# MJE13001_SWITCHING_WITH_FEEDBACK_V2.net
KiCad netlist of a schematic drawn in Altium Designer
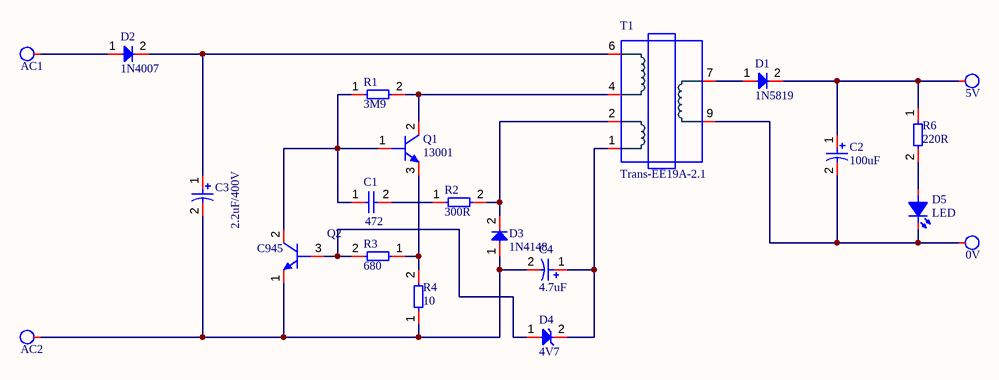
[diagram p0: MJE13001_SWITCHING_WITH_FEEDBACK_V2.SchDoc]

(export (version "E")
  (design (tool "Eeschema 10.0.6"))
  (components
    (comp (ref "0V")
      (value "SolderPoint")
      (footprint "SolderPoint")
      (libsource (lib "Lib31082020") (part "SolderPoint"))
    )
    (comp (ref "5V")
      (value "SolderPoint")
      (footprint "SolderPoint")
      (libsource (lib "Lib31082020") (part "SolderPoint"))
    )
    (comp (ref "AC1")
      (value "SolderPoint")
      (footprint "SolderPoint")
      (libsource (lib "Lib31082020") (part "SolderPoint"))
    )
    (comp (ref "AC2")
      (value "SolderPoint")
      (footprint "SolderPoint")
      (libsource (lib "Lib31082020") (part "SolderPoint"))
    )
    (comp (ref "C1")
      (value "472")
      (footprint "CAP_Ceramic_Disc_2")
      (libsource (lib "Lib31082020") (part "Capacitors(Disc)"))
    )
    (comp (ref "C2")
      (value "100uF")
      (footprint "CAP_RAD_2.5mm")
      (libsource (lib "Lib31082020") (part "Capacitor(Radian)"))
    )
    (comp (ref "C3")
      (value "2.2uF/400V")
      (footprint "CAP_RAD_3.5mm")
      (libsource (lib "Lib31082020") (part "Capacitor(Radian)"))
    )
    (comp (ref "C4")
      (value "4.7uF")
      (footprint "CAP_RAD_2.5mm")
      (libsource (lib "Lib31082020") (part "Capacitor(Radian)"))
    )
    (comp (ref "D1") (value "1N5819") (footprint "DO-41") (libsource (lib "Lib31082020") (part "1N4937")))
    (comp (ref "D2") (value "1N4007") (footprint "DO-41") (libsource (lib "Lib31082020") (part "1N4007")))
    (comp (ref "D3")
      (value "1N4148")
      (footprint "DO-35 Horizontal")
      (libsource (lib "Lib31082020") (part "Diode 1N4148"))
    )
    (comp (ref "D4")
      (value "4V7")
      (footprint "DO-35 Horizontal")
      (libsource (lib "Lib31082020") (part "Diode Zener"))
    )
    (comp (ref "D5") (value "LED") (footprint "LED_3MM_RED") (libsource (lib "Lib31082020") (part "LED 3MM")))
    (comp (ref "Q1")
      (value "13001")
      (footprint "TO-92")
      (libsource (lib "Lib31082020") (part "MJE13001_Type_F"))
    )
    (comp (ref "Q2") (value "C945") (footprint "TO-92") (libsource (lib "Lib31082020") (part "C945")))
    (comp (ref "R1") (value "3M9") (footprint "RES-0.25W-H-MF") (libsource (lib "") (part "Resistors THD_2")))
    (comp (ref "R2")
      (value "300R")
      (footprint "RES-0.25W-H-MF")
      (libsource (lib "") (part "Resistors THD_2"))
    )
    (comp (ref "R3") (value "680") (footprint "RES-0.25W-H-MF") (libsource (lib "") (part "Resistors THD_3")))
    (comp (ref "R4") (value "10") (footprint "RES-0.25W-H-MF") (libsource (lib "") (part "Resistors THD_1")))
    (comp (ref "R6")
      (value "220R")
      (footprint "RES-0.25W-H-MF")
      (libsource (lib "Lib31082020") (part "Resistors THD"))
    )
    (comp (ref "T1")
      (value "Trans-EE19A-2.1")
      (footprint "TRANS_EE19A-2.1")
      (libsource (lib "Lib31082020") (part "Trans-EE19A-2.1"))
    )
  )
  (nets
    (net (code "1") (name "Net-(5V-Pad1)") (class "Default")
      (node (ref "5V") (pin "1") (pinfunction "1_1") (pintype "passive"))
      (node (ref "C2") (pin "1") (pinfunction "1_1") (pintype "passive"))
      (node (ref "D1") (pin "2") (pinfunction "2_2") (pintype "passive"))
      (node (ref "R6") (pin "1") (pinfunction "1_1") (pintype "passive"))
    )
    (net (code "2") (name "Net-(AC1-Pad1)") (class "Default")
      (node (ref "AC1") (pin "1") (pinfunction "1_1") (pintype "passive"))
      (node (ref "D2") (pin "1") (pinfunction "1_1") (pintype "passive"))
    )
    (net (code "3") (name "Net-(C1-Pad2)") (class "Default")
      (node (ref "C1") (pin "2") (pinfunction "2_2") (pintype "passive"))
      (node (ref "R2") (pin "1") (pinfunction "1_1") (pintype "passive"))
    )
    (net (code "4") (name "Net-(C4-Pad1)") (class "Default")
      (node (ref "C4") (pin "1") (pinfunction "1_1") (pintype "passive"))
      (node (ref "D4") (pin "2") (pinfunction "2_2") (pintype "passive"))
      (node (ref "T1") (pin "1") (pinfunction "1_1") (pintype "passive"))
    )
    (net (code "5") (name "Net-(D1-Pad1)") (class "Default")
      (node (ref "D1") (pin "1") (pinfunction "1_1") (pintype "passive"))
      (node (ref "T1") (pin "7") (pinfunction "7_7") (pintype "passive"))
    )
    (net (code "6") (name "Net-(D3-Pad2)") (class "Default")
      (node (ref "D3") (pin "2") (pinfunction "2_2") (pintype "passive"))
      (node (ref "R2") (pin "2") (pinfunction "2_2") (pintype "passive"))
      (node (ref "T1") (pin "2") (pinfunction "2_2") (pintype "passive"))
    )
    (net (code "7") (name "Net-(D5-A)") (class "Default")
      (node (ref "D5") (pin "1") (pinfunction "A_1") (pintype "passive"))
      (node (ref "R6") (pin "2") (pinfunction "2_2") (pintype "passive"))
    )
    (net (code "8") (name "Net-(D5-K)") (class "Default")
      (node (ref "0V") (pin "1") (pinfunction "1_1") (pintype "passive"))
      (node (ref "C2") (pin "2") (pinfunction "2_2") (pintype "passive"))
      (node (ref "D5") (pin "2") (pinfunction "K_2") (pintype "passive"))
      (node (ref "T1") (pin "9") (pinfunction "9_9") (pintype "passive"))
    )
    (net (code "9") (name "Net-(Q1-B)") (class "Default")
      (node (ref "C1") (pin "1") (pinfunction "1_1") (pintype "passive"))
      (node (ref "Q1") (pin "1") (pinfunction "B_1") (pintype "passive"))
      (node (ref "Q2") (pin "2") (pinfunction "C_2") (pintype "passive"))
      (node (ref "R1") (pin "1") (pinfunction "1_1") (pintype "passive"))
    )
    (net (code "10") (name "Net-(Q1-C)") (class "Default")
      (node (ref "Q1") (pin "2") (pinfunction "C_2") (pintype "passive"))
      (node (ref "R1") (pin "2") (pinfunction "2_2") (pintype "passive"))
      (node (ref "T1") (pin "4") (pinfunction "4_4") (pintype "passive"))
    )
    (net (code "11") (name "Net-(Q1-E)") (class "Default")
      (node (ref "Q1") (pin "3") (pinfunction "E_3") (pintype "passive"))
      (node (ref "R3") (pin "1") (pinfunction "1_1") (pintype "passive"))
      (node (ref "R4") (pin "2") (pinfunction "2_2") (pintype "passive"))
    )
    (net (code "12") (name "Net-(Q2-B)") (class "Default")
      (node (ref "D4") (pin "1") (pinfunction "1_1") (pintype "passive"))
      (node (ref "Q2") (pin "3") (pinfunction "B_3") (pintype "passive"))
      (node (ref "R3") (pin "2") (pinfunction "2_2") (pintype "passive"))
    )
    (net (code "13") (name "Net-(Q2-E)") (class "Default")
      (node (ref "AC2") (pin "1") (pinfunction "1_1") (pintype "passive"))
      (node (ref "C3") (pin "2") (pinfunction "2_2") (pintype "passive"))
      (node (ref "C4") (pin "2") (pinfunction "2_2") (pintype "passive"))
      (node (ref "D3") (pin "1") (pinfunction "1_1") (pintype "passive"))
      (node (ref "Q2") (pin "1") (pinfunction "E_1") (pintype "passive"))
      (node (ref "R4") (pin "1") (pinfunction "1_1") (pintype "passive"))
    )
    (net (code "14") (name "Net-(T1-61)") (class "Default")
      (node (ref "C3") (pin "1") (pinfunction "1_1") (pintype "passive"))
      (node (ref "D2") (pin "2") (pinfunction "2_2") (pintype "passive"))
      (node (ref "T1") (pin "6") (pinfunction "61_6") (pintype "passive"))
    )
  )
)
